# v2.net
KiCad netlist of a schematic drawn in EAGLE
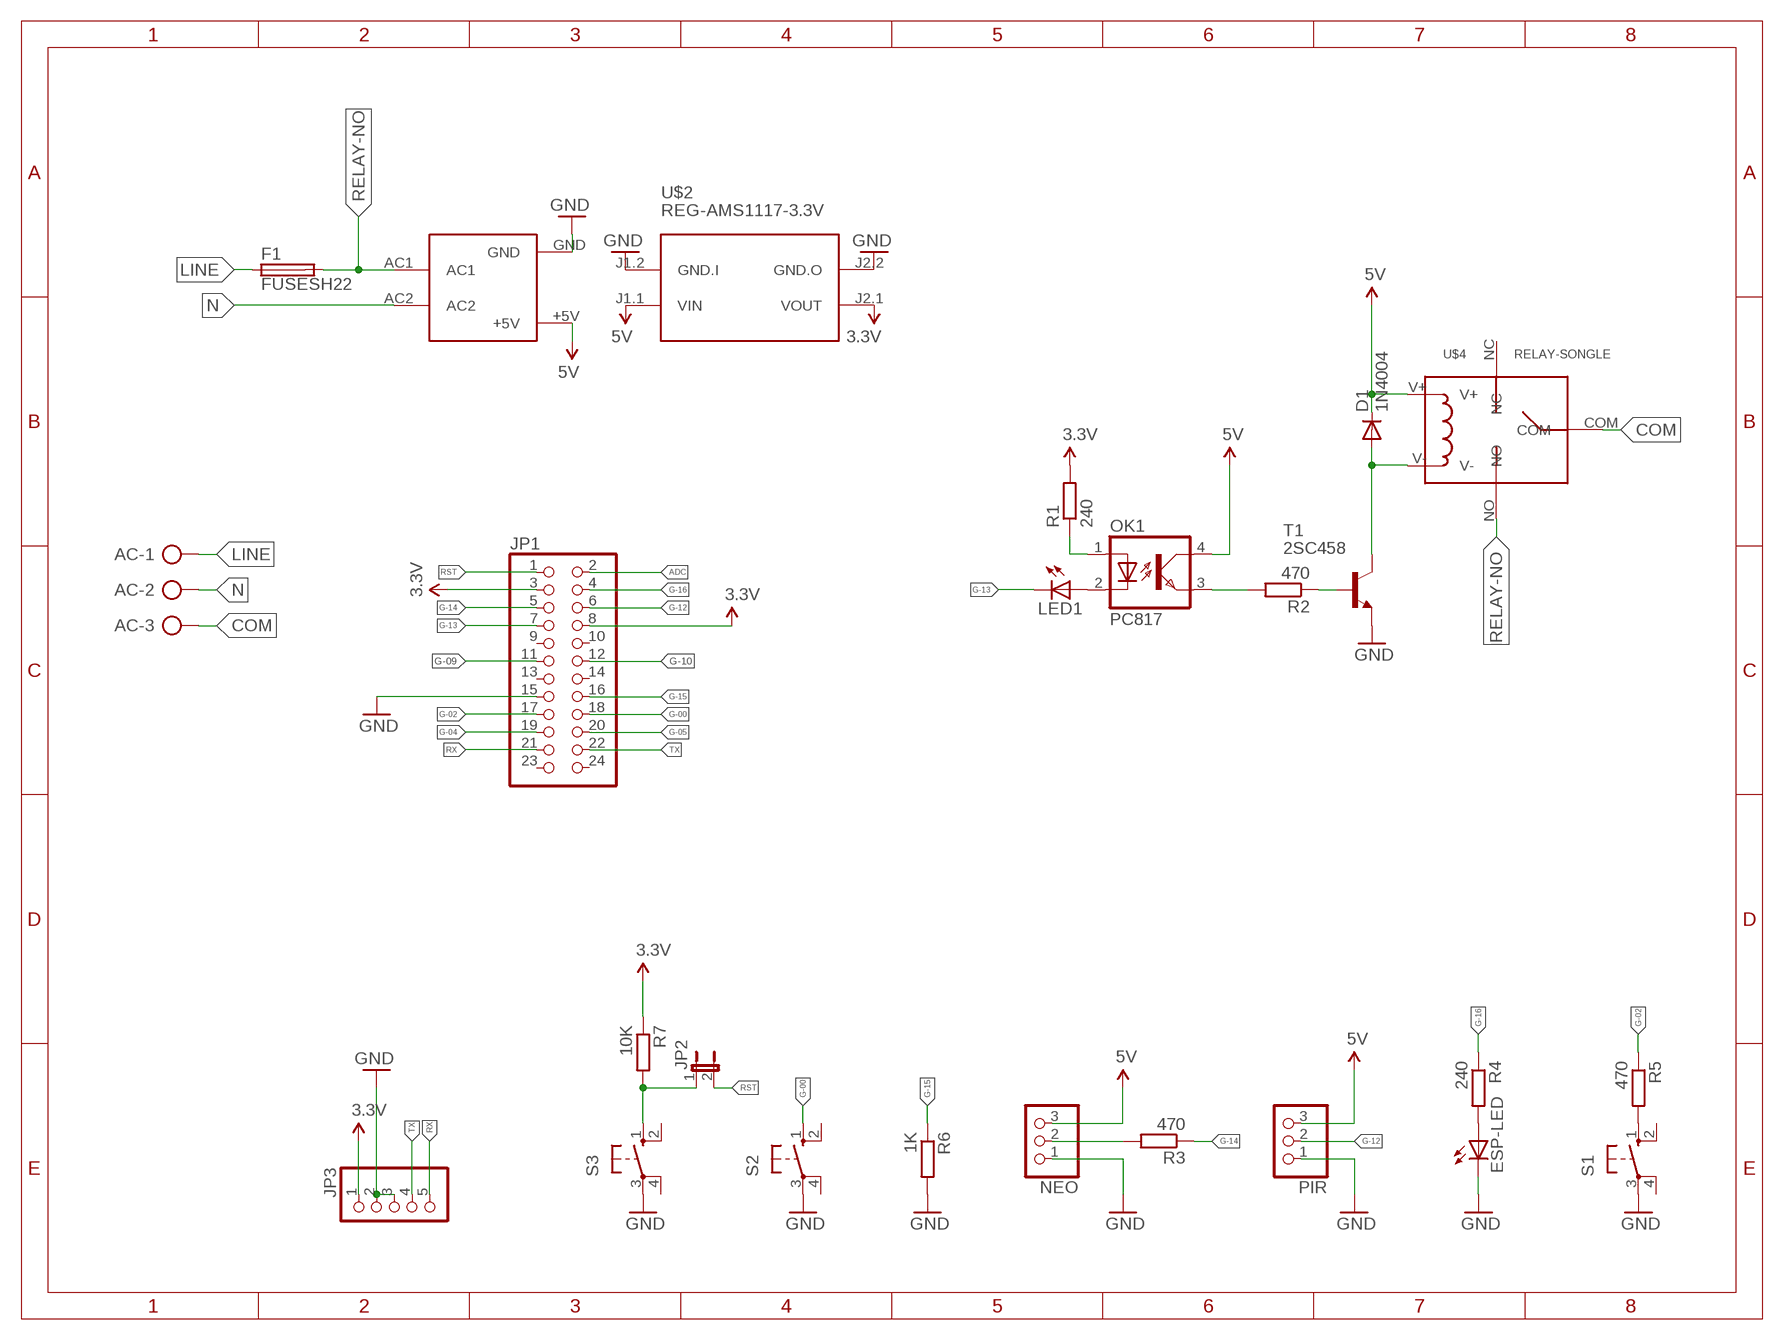
[diagram p0: schematic, sheet 1]

(export (version "E")
  (design (tool "Eeschema 10.0.6"))
  (components
    (comp (ref "AC")
      (value "AK300/3")
      (footprint "eagle-import:AK300_3")
      (libsource (lib "eagle-import") (part "AK300/3"))
    )
    (comp (ref "D1")
      (value "1N4004")
      (footprint "eagle-import:DO41-10")
      (libsource (lib "eagle-import") (part "1N4004"))
    )
    (comp (ref "ESP-LED")
      (value "LED5MM")
      (footprint "eagle-import:LED5MM")
      (libsource (lib "eagle-import") (part "LED5MM"))
    )
    (comp (ref "F1")
      (value "FUSESH22")
      (footprint "eagle-import:SH22")
      (libsource (lib "eagle-import") (part "FUSESH22"))
    )
    (comp (ref "JP1")
      (value "PINHD-2X12")
      (footprint "eagle-import:2X12")
      (libsource (lib "eagle-import") (part "PINHD-2X12"))
    )
    (comp (ref "JP2")
      (value "JUMPER-2PTH")
      (footprint "eagle-import:1X02")
      (libsource (lib "eagle-import") (part "JUMPER-2PTH"))
    )
    (comp (ref "JP3")
      (value "PINHD-1X5")
      (footprint "eagle-import:1X05")
      (libsource (lib "eagle-import") (part "PINHD-1X5"))
    )
    (comp (ref "LED1")
      (value "LED5MM")
      (footprint "eagle-import:LED5MM")
      (libsource (lib "eagle-import") (part "LED5MM"))
    )
    (comp (ref "NEO")
      (value "PINHD-1X3")
      (footprint "eagle-import:1X03")
      (libsource (lib "eagle-import") (part "PINHD-1X3"))
    )
    (comp (ref "OK1")
      (value "PC817")
      (footprint "eagle-import:DIL04")
      (fields (field (name "MPN") "PC817X4J000F"))
      (libsource (lib "eagle-import") (part "PC817"))
    )
    (comp (ref "PIR")
      (value "PINHD-1X3")
      (footprint "eagle-import:1X03")
      (libsource (lib "eagle-import") (part "PINHD-1X3"))
    )
    (comp (ref "R1")
      (value "240")
      (footprint "eagle-import:0204_5")
      (libsource (lib "eagle-import") (part "R-EU_0204/5"))
    )
    (comp (ref "R2")
      (value "470")
      (footprint "eagle-import:0204_5")
      (libsource (lib "eagle-import") (part "R-EU_0204/5"))
    )
    (comp (ref "R3")
      (value "470")
      (footprint "eagle-import:0204_5")
      (libsource (lib "eagle-import") (part "R-EU_0204/5"))
    )
    (comp (ref "R4")
      (value "240")
      (footprint "eagle-import:0204_5")
      (libsource (lib "eagle-import") (part "R-EU_0204/5"))
    )
    (comp (ref "R5")
      (value "470")
      (footprint "eagle-import:0204_5")
      (libsource (lib "eagle-import") (part "R-EU_0204/5"))
    )
    (comp (ref "R6")
      (value "1K")
      (footprint "eagle-import:0204_5")
      (libsource (lib "eagle-import") (part "R-EU_0204/5"))
    )
    (comp (ref "R7")
      (value "10K")
      (footprint "eagle-import:0204_5")
      (libsource (lib "eagle-import") (part "R-EU_0204/5"))
    )
    (comp (ref "S1")
      (value "10-XX")
      (footprint "eagle-import:B3F-10XX")
      (fields (field (name "MPN") "B3F-1000"))
      (libsource (lib "eagle-import") (part "10-XX"))
    )
    (comp (ref "S2")
      (value "10-XX")
      (footprint "eagle-import:B3F-10XX")
      (fields (field (name "MPN") "B3F-1000"))
      (libsource (lib "eagle-import") (part "10-XX"))
    )
    (comp (ref "S3")
      (value "10-XX")
      (footprint "eagle-import:B3F-10XX")
      (fields (field (name "MPN") "B3F-1000"))
      (libsource (lib "eagle-import") (part "10-XX"))
    )
    (comp (ref "T1")
      (value "2SC458")
      (footprint "eagle-import:TO92-ECB")
      (libsource (lib "eagle-import") (part "2SC458"))
    )
    (comp (ref "U$1")
      (value "HLK-PM01")
      (footprint "eagle-import:HLK-PM01")
      (libsource (lib "eagle-import") (part "HLK-PM01"))
    )
    (comp (ref "U$2")
      (value "REG-AMS1117-3.3V")
      (footprint "eagle-import:REG-AMS1117")
      (libsource (lib "eagle-import") (part "REG-AMS1117-3.3V"))
    )
    (comp (ref "U$4")
      (value "RELAY-SONGLE")
      (footprint "eagle-import:RELAY-SONGLE")
      (libsource (lib "eagle-import") (part "RELAY-SONGLE"))
    )
  )
  (nets
    (net (code "1") (name "3.3V") (class "Default")
      (node (ref "JP1") (pin "3") (pinfunction "3_3") (pintype "passive"))
      (node (ref "JP1") (pin "8") (pinfunction "8_8") (pintype "passive"))
      (node (ref "JP3") (pin "1") (pinfunction "1_1") (pintype "passive"))
      (node (ref "R1") (pin "2") (pinfunction "2_2") (pintype "passive"))
      (node (ref "R7") (pin "1") (pinfunction "1_1") (pintype "passive"))
      (node (ref "U$2") (pin "J2.1") (pinfunction "VOUT_J2.1") (pintype "bidirectional"))
    )
    (net (code "2") (name "5V") (class "Default")
      (node (ref "D1") (pin "C") (pinfunction "C_C") (pintype "passive"))
      (node (ref "NEO") (pin "3") (pinfunction "3_3") (pintype "passive"))
      (node (ref "OK1") (pin "4") (pinfunction "COL_4") (pintype "passive"))
      (node (ref "PIR") (pin "3") (pinfunction "3_3") (pintype "passive"))
      (node (ref "U$1") (pin "+5V") (pinfunction "+5V_+5V") (pintype "bidirectional"))
      (node (ref "U$2") (pin "J1.1") (pinfunction "VIN_J1.1") (pintype "bidirectional"))
      (node (ref "U$4") (pin "V+") (pinfunction "V+_V+") (pintype "bidirectional"))
    )
    (net (code "3") (name "ADC") (class "Default")
      (node (ref "JP1") (pin "2") (pinfunction "2_2") (pintype "passive"))
    )
    (net (code "4") (name "COM") (class "Default")
      (node (ref "AC") (pin "3") (pinfunction "KL_3") (pintype "passive"))
      (node (ref "U$4") (pin "COM") (pinfunction "COM_COM") (pintype "bidirectional"))
    )
    (net (code "5") (name "G-00") (class "Default")
      (node (ref "JP1") (pin "18") (pinfunction "18_18") (pintype "passive"))
      (node (ref "S2") (pin "1") (pinfunction "S_1") (pintype "passive"))
    )
    (net (code "6") (name "G-02") (class "Default")
      (node (ref "JP1") (pin "17") (pinfunction "17_17") (pintype "passive"))
      (node (ref "R5") (pin "1") (pinfunction "1_1") (pintype "passive"))
    )
    (net (code "7") (name "G-04") (class "Default")
      (node (ref "JP1") (pin "19") (pinfunction "19_19") (pintype "passive"))
    )
    (net (code "8") (name "G-05") (class "Default")
      (node (ref "JP1") (pin "20") (pinfunction "20_20") (pintype "passive"))
    )
    (net (code "9") (name "G-09") (class "Default")
      (node (ref "JP1") (pin "11") (pinfunction "11_11") (pintype "passive"))
    )
    (net (code "10") (name "G-10") (class "Default")
      (node (ref "JP1") (pin "12") (pinfunction "12_12") (pintype "passive"))
    )
    (net (code "11") (name "G-12") (class "Default")
      (node (ref "JP1") (pin "6") (pinfunction "6_6") (pintype "passive"))
      (node (ref "PIR") (pin "2") (pinfunction "2_2") (pintype "passive"))
    )
    (net (code "12") (name "G-13") (class "Default")
      (node (ref "JP1") (pin "7") (pinfunction "7_7") (pintype "passive"))
      (node (ref "LED1") (pin "K") (pinfunction "C_K") (pintype "passive"))
    )
    (net (code "13") (name "G-14") (class "Default")
      (node (ref "JP1") (pin "5") (pinfunction "5_5") (pintype "passive"))
      (node (ref "R3") (pin "1") (pinfunction "1_1") (pintype "passive"))
    )
    (net (code "14") (name "G-15") (class "Default")
      (node (ref "JP1") (pin "16") (pinfunction "16_16") (pintype "passive"))
      (node (ref "R6") (pin "1") (pinfunction "1_1") (pintype "passive"))
    )
    (net (code "15") (name "G-16") (class "Default")
      (node (ref "JP1") (pin "4") (pinfunction "4_4") (pintype "passive"))
      (node (ref "R4") (pin "1") (pinfunction "1_1") (pintype "passive"))
    )
    (net (code "16") (name "GND") (class "Default")
      (node (ref "ESP-LED") (pin "K") (pinfunction "C_K") (pintype "passive"))
      (node (ref "JP1") (pin "15") (pinfunction "15_15") (pintype "passive"))
      (node (ref "JP3") (pin "2") (pinfunction "2_2") (pintype "passive"))
      (node (ref "JP3") (pin "3") (pinfunction "3_3") (pintype "passive"))
      (node (ref "NEO") (pin "1") (pinfunction "1_1") (pintype "passive"))
      (node (ref "PIR") (pin "1") (pinfunction "1_1") (pintype "passive"))
      (node (ref "R6") (pin "2") (pinfunction "2_2") (pintype "passive"))
      (node (ref "S1") (pin "3") (pinfunction "P_3") (pintype "passive"))
      (node (ref "S2") (pin "3") (pinfunction "P_3") (pintype "passive"))
      (node (ref "S3") (pin "3") (pinfunction "P_3") (pintype "passive"))
      (node (ref "T1") (pin "E") (pinfunction "E_E") (pintype "passive"))
      (node (ref "U$1") (pin "GND") (pinfunction "GND_GND") (pintype "bidirectional"))
      (node (ref "U$2") (pin "J1.2") (pinfunction "GND.I_J1.2") (pintype "bidirectional"))
      (node (ref "U$2") (pin "J2.2") (pinfunction "GND.O_J2.2") (pintype "bidirectional"))
    )
    (net (code "17") (name "LINE") (class "Default")
      (node (ref "AC") (pin "1") (pinfunction "KL_1") (pintype "passive"))
      (node (ref "F1") (pin "1") (pinfunction "1_1") (pintype "passive"))
    )
    (net (code "18") (name "N") (class "Default")
      (node (ref "AC") (pin "2") (pinfunction "KL_2") (pintype "passive"))
      (node (ref "U$1") (pin "AC2") (pinfunction "AC2_AC2") (pintype "bidirectional"))
    )
    (net (code "19") (name "Net-(D1-PadA)") (class "Default")
      (node (ref "D1") (pin "A") (pinfunction "A_A") (pintype "passive"))
      (node (ref "T1") (pin "C") (pinfunction "C_C") (pintype "passive"))
      (node (ref "U$4") (pin "V-") (pinfunction "V-_V-") (pintype "bidirectional"))
    )
    (net (code "20") (name "Net-(ESP-LED-PadA)") (class "Default")
      (node (ref "ESP-LED") (pin "A") (pinfunction "A_A") (pintype "passive"))
      (node (ref "R4") (pin "2") (pinfunction "2_2") (pintype "passive"))
    )
    (net (code "21") (name "Net-(NEO-Pad2)") (class "Default")
      (node (ref "NEO") (pin "2") (pinfunction "2_2") (pintype "passive"))
      (node (ref "R3") (pin "2") (pinfunction "2_2") (pintype "passive"))
    )
    (net (code "22") (name "Net-(OK1-A)") (class "Default")
      (node (ref "OK1") (pin "1") (pinfunction "A_1") (pintype "passive"))
      (node (ref "R1") (pin "1") (pinfunction "1_1") (pintype "passive"))
    )
    (net (code "23") (name "Net-(OK1-C)") (class "Default")
      (node (ref "LED1") (pin "A") (pinfunction "A_A") (pintype "passive"))
      (node (ref "OK1") (pin "2") (pinfunction "C_2") (pintype "passive"))
    )
    (net (code "24") (name "Net-(OK1-EMIT)") (class "Default")
      (node (ref "OK1") (pin "3") (pinfunction "EMIT_3") (pintype "passive"))
      (node (ref "R2") (pin "2") (pinfunction "2_2") (pintype "passive"))
    )
    (net (code "25") (name "Net-(R2-Pad1)") (class "Default")
      (node (ref "R2") (pin "1") (pinfunction "1_1") (pintype "passive"))
      (node (ref "T1") (pin "B") (pinfunction "B_B") (pintype "passive"))
    )
    (net (code "26") (name "Net-(S1-S)") (class "Default")
      (node (ref "R5") (pin "2") (pinfunction "2_2") (pintype "passive"))
      (node (ref "S1") (pin "1") (pinfunction "S_1") (pintype "passive"))
    )
    (net (code "27") (name "Net-(S3-S)") (class "Default")
      (node (ref "JP2") (pin "1") (pinfunction "1_1") (pintype "passive"))
      (node (ref "R7") (pin "2") (pinfunction "2_2") (pintype "passive"))
      (node (ref "S3") (pin "1") (pinfunction "S_1") (pintype "passive"))
    )
    (net (code "28") (name "RELAY-NO") (class "Default")
      (node (ref "F1") (pin "2") (pinfunction "2_2") (pintype "passive"))
      (node (ref "U$1") (pin "AC1") (pinfunction "AC1_AC1") (pintype "bidirectional"))
      (node (ref "U$4") (pin "NO") (pinfunction "NO_NO") (pintype "bidirectional"))
    )
    (net (code "29") (name "RST") (class "Default")
      (node (ref "JP1") (pin "1") (pinfunction "1_1") (pintype "passive"))
      (node (ref "JP2") (pin "2") (pinfunction "2_2") (pintype "passive"))
    )
    (net (code "30") (name "RX") (class "Default")
      (node (ref "JP1") (pin "21") (pinfunction "21_21") (pintype "passive"))
      (node (ref "JP3") (pin "5") (pinfunction "5_5") (pintype "passive"))
    )
    (net (code "31") (name "TX") (class "Default")
      (node (ref "JP1") (pin "22") (pinfunction "22_22") (pintype "passive"))
      (node (ref "JP3") (pin "4") (pinfunction "4_4") (pintype "passive"))
    )
    (net (code "32") (name "unconnected-(JP1-Pad9)") (class "Default")
      (node (ref "JP1") (pin "9") (pinfunction "9_9") (pintype "passive"))
    )
    (net (code "33") (name "unconnected-(JP1-Pad10)") (class "Default")
      (node (ref "JP1") (pin "10") (pinfunction "10_10") (pintype "passive"))
    )
    (net (code "34") (name "unconnected-(JP1-Pad13)") (class "Default")
      (node (ref "JP1") (pin "13") (pinfunction "13_13") (pintype "passive"))
    )
    (net (code "35") (name "unconnected-(JP1-Pad14)") (class "Default")
      (node (ref "JP1") (pin "14") (pinfunction "14_14") (pintype "passive"))
    )
    (net (code "36") (name "unconnected-(JP1-Pad23)") (class "Default")
      (node (ref "JP1") (pin "23") (pinfunction "23_23") (pintype "passive"))
    )
    (net (code "37") (name "unconnected-(JP1-Pad24)") (class "Default")
      (node (ref "JP1") (pin "24") (pinfunction "24_24") (pintype "passive"))
    )
    (net (code "38") (name "unconnected-(S1-P1-Pad4)") (class "Default")
      (node (ref "S1") (pin "4") (pinfunction "P1_4") (pintype "passive"))
    )
    (net (code "39") (name "unconnected-(S1-S1-Pad2)") (class "Default")
      (node (ref "S1") (pin "2") (pinfunction "S1_2") (pintype "passive"))
    )
    (net (code "40") (name "unconnected-(S2-P1-Pad4)") (class "Default")
      (node (ref "S2") (pin "4") (pinfunction "P1_4") (pintype "passive"))
    )
    (net (code "41") (name "unconnected-(S2-S1-Pad2)") (class "Default")
      (node (ref "S2") (pin "2") (pinfunction "S1_2") (pintype "passive"))
    )
    (net (code "42") (name "unconnected-(S3-P1-Pad4)") (class "Default")
      (node (ref "S3") (pin "4") (pinfunction "P1_4") (pintype "passive"))
    )
    (net (code "43") (name "unconnected-(S3-S1-Pad2)") (class "Default")
      (node (ref "S3") (pin "2") (pinfunction "S1_2") (pintype "passive"))
    )
    (net (code "44") (name "unconnected-(U$4-PadNC)") (class "Default")
      (node (ref "U$4") (pin "NC") (pinfunction "NC_NC") (pintype "bidirectional"))
    )
  )
)
